# Multiplier.net
KiCad netlist of a schematic drawn in EAGLE
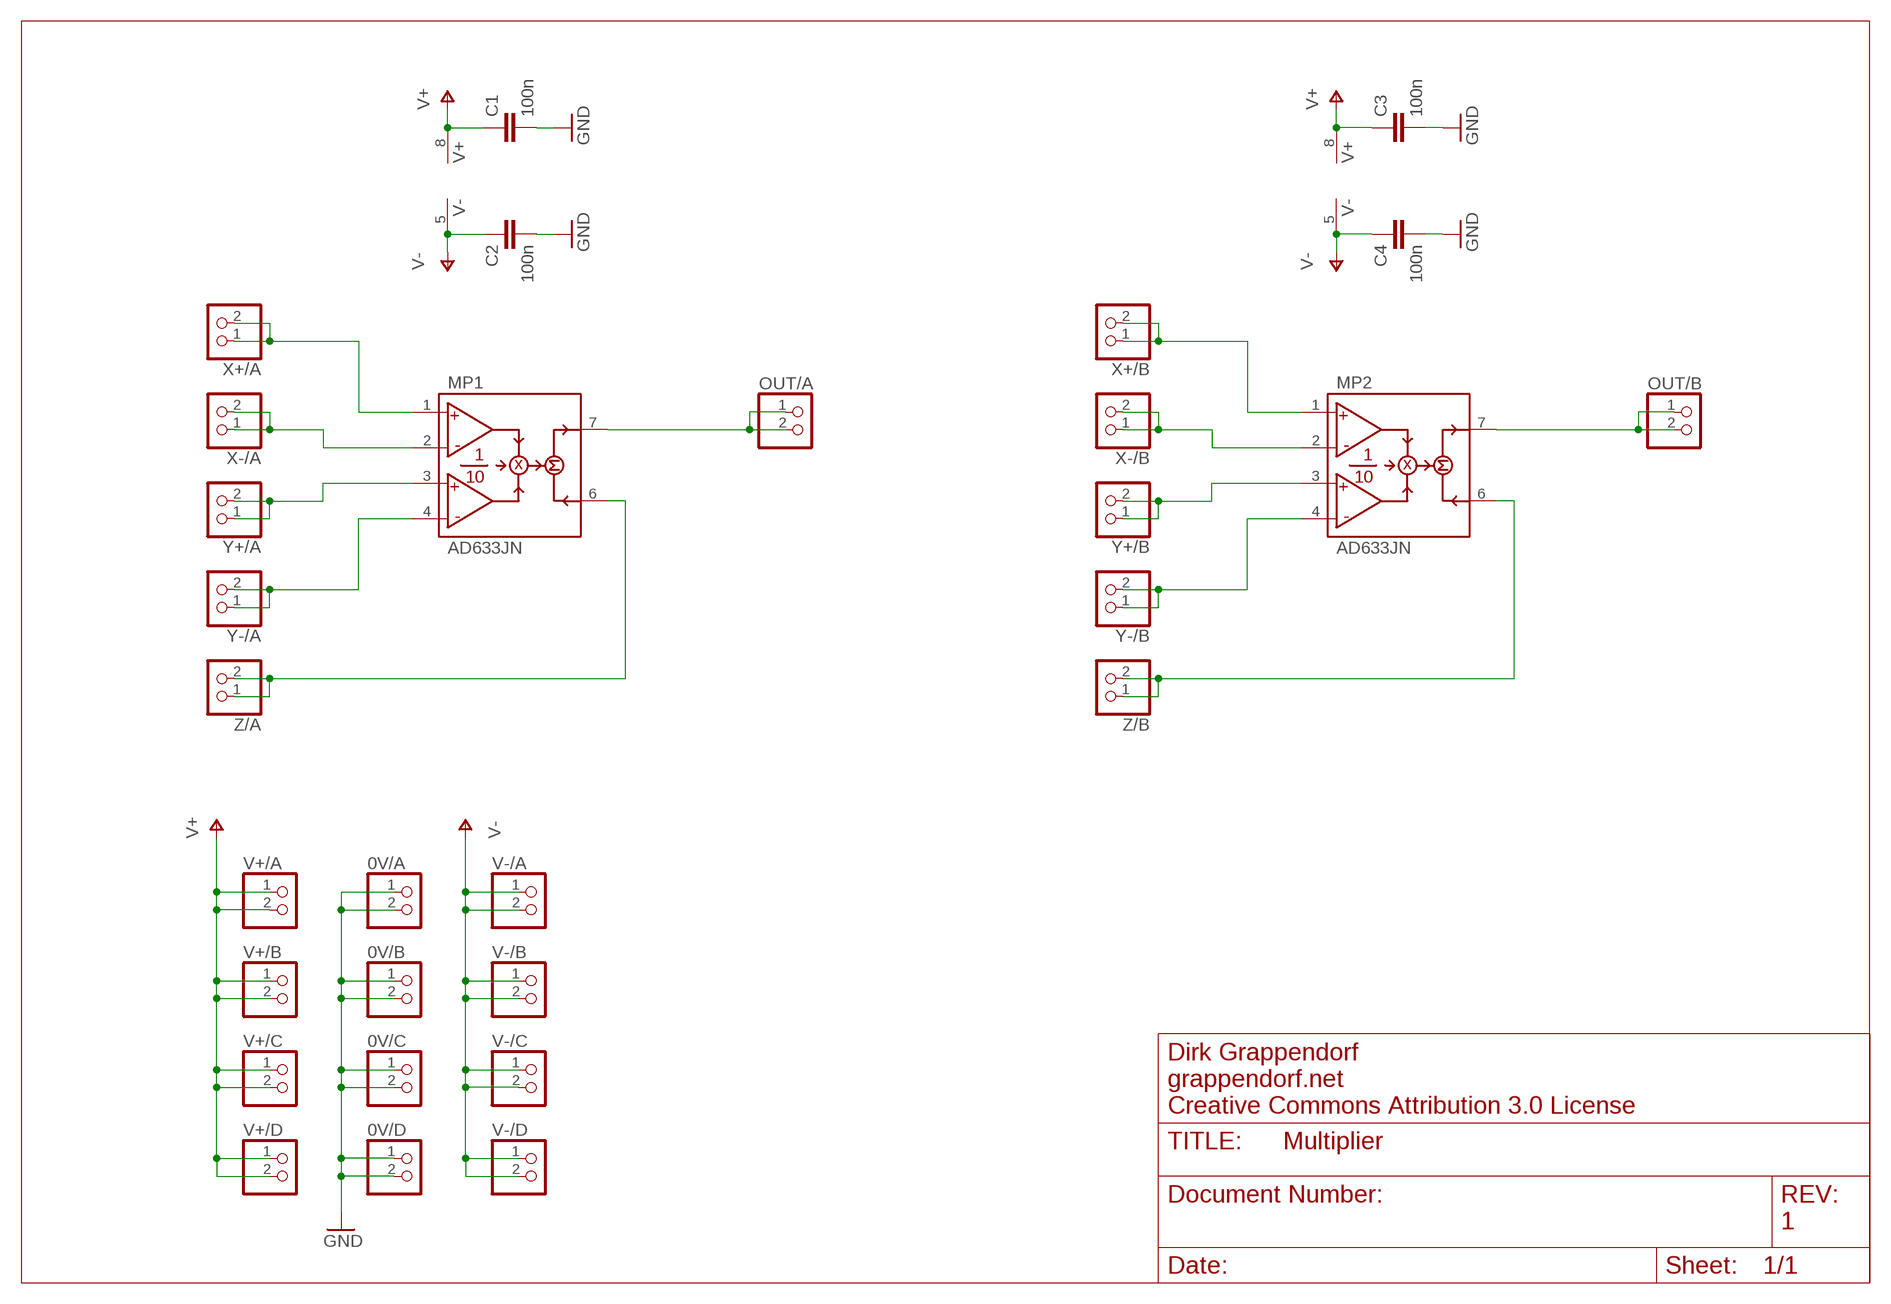
[diagram p0: schematic, sheet 1]

(export (version "E")
  (design (tool "Eeschema 10.0.6"))
  (components
    (comp (ref "0V/A")
      (value "PINHD-1X2")
      (footprint "eagle-import:1X02")
      (libsource (lib "eagle-import") (part "PINHD-1X2"))
    )
    (comp (ref "0V/B")
      (value "PINHD-1X2")
      (footprint "eagle-import:1X02")
      (libsource (lib "eagle-import") (part "PINHD-1X2"))
    )
    (comp (ref "0V/C")
      (value "PINHD-1X2")
      (footprint "eagle-import:1X02")
      (libsource (lib "eagle-import") (part "PINHD-1X2"))
    )
    (comp (ref "0V/D")
      (value "PINHD-1X2")
      (footprint "eagle-import:1X02")
      (libsource (lib "eagle-import") (part "PINHD-1X2"))
    )
    (comp (ref "C1")
      (value "100n")
      (footprint "eagle-import:C025-025X050")
      (libsource (lib "eagle-import") (part "C-EU025-025X050"))
    )
    (comp (ref "C2")
      (value "100n")
      (footprint "eagle-import:C025-025X050")
      (libsource (lib "eagle-import") (part "C-EU025-025X050"))
    )
    (comp (ref "C3")
      (value "100n")
      (footprint "eagle-import:C025-025X050")
      (libsource (lib "eagle-import") (part "C-EU025-025X050"))
    )
    (comp (ref "C4")
      (value "100n")
      (footprint "eagle-import:C025-025X050")
      (libsource (lib "eagle-import") (part "C-EU025-025X050"))
    )
    (comp (ref "MP1")
      (value "AD633JN")
      (footprint "eagle-import:DIL08")
      (libsource (lib "eagle-import") (part "AD633NJ"))
    )
    (comp (ref "MP2")
      (value "AD633JN")
      (footprint "eagle-import:DIL08")
      (libsource (lib "eagle-import") (part "AD633NJ"))
    )
    (comp (ref "OUT/A")
      (value "PINHD-1X2")
      (footprint "eagle-import:1X02")
      (libsource (lib "eagle-import") (part "PINHD-1X2"))
    )
    (comp (ref "OUT/B")
      (value "PINHD-1X2")
      (footprint "eagle-import:1X02")
      (libsource (lib "eagle-import") (part "PINHD-1X2"))
    )
    (comp (ref "V+/A")
      (value "PINHD-1X2")
      (footprint "eagle-import:1X02")
      (libsource (lib "eagle-import") (part "PINHD-1X2"))
    )
    (comp (ref "V+/B")
      (value "PINHD-1X2")
      (footprint "eagle-import:1X02")
      (libsource (lib "eagle-import") (part "PINHD-1X2"))
    )
    (comp (ref "V+/C")
      (value "PINHD-1X2")
      (footprint "eagle-import:1X02")
      (libsource (lib "eagle-import") (part "PINHD-1X2"))
    )
    (comp (ref "V+/D")
      (value "PINHD-1X2")
      (footprint "eagle-import:1X02")
      (libsource (lib "eagle-import") (part "PINHD-1X2"))
    )
    (comp (ref "V-/A")
      (value "PINHD-1X2")
      (footprint "eagle-import:1X02")
      (libsource (lib "eagle-import") (part "PINHD-1X2"))
    )
    (comp (ref "V-/B")
      (value "PINHD-1X2")
      (footprint "eagle-import:1X02")
      (libsource (lib "eagle-import") (part "PINHD-1X2"))
    )
    (comp (ref "V-/C")
      (value "PINHD-1X2")
      (footprint "eagle-import:1X02")
      (libsource (lib "eagle-import") (part "PINHD-1X2"))
    )
    (comp (ref "V-/D")
      (value "PINHD-1X2")
      (footprint "eagle-import:1X02")
      (libsource (lib "eagle-import") (part "PINHD-1X2"))
    )
    (comp (ref "X+/A")
      (value "PINHD-1X2")
      (footprint "eagle-import:1X02")
      (libsource (lib "eagle-import") (part "PINHD-1X2"))
    )
    (comp (ref "X+/B")
      (value "PINHD-1X2")
      (footprint "eagle-import:1X02")
      (libsource (lib "eagle-import") (part "PINHD-1X2"))
    )
    (comp (ref "X-/A")
      (value "PINHD-1X2")
      (footprint "eagle-import:1X02")
      (libsource (lib "eagle-import") (part "PINHD-1X2"))
    )
    (comp (ref "X-/B")
      (value "PINHD-1X2")
      (footprint "eagle-import:1X02")
      (libsource (lib "eagle-import") (part "PINHD-1X2"))
    )
    (comp (ref "Y+/A")
      (value "PINHD-1X2")
      (footprint "eagle-import:1X02")
      (libsource (lib "eagle-import") (part "PINHD-1X2"))
    )
    (comp (ref "Y+/B")
      (value "PINHD-1X2")
      (footprint "eagle-import:1X02")
      (libsource (lib "eagle-import") (part "PINHD-1X2"))
    )
    (comp (ref "Y-/A")
      (value "PINHD-1X2")
      (footprint "eagle-import:1X02")
      (libsource (lib "eagle-import") (part "PINHD-1X2"))
    )
    (comp (ref "Y-/B")
      (value "PINHD-1X2")
      (footprint "eagle-import:1X02")
      (libsource (lib "eagle-import") (part "PINHD-1X2"))
    )
    (comp (ref "Z/A")
      (value "PINHD-1X2")
      (footprint "eagle-import:1X02")
      (libsource (lib "eagle-import") (part "PINHD-1X2"))
    )
    (comp (ref "Z/B")
      (value "PINHD-1X2")
      (footprint "eagle-import:1X02")
      (libsource (lib "eagle-import") (part "PINHD-1X2"))
    )
  )
  (nets
    (net (code "1") (name "GND") (class "Default")
      (node (ref "0V/A") (pin "1") (pinfunction "1_1") (pintype "passive"))
      (node (ref "0V/A") (pin "2") (pinfunction "2_2") (pintype "passive"))
      (node (ref "0V/B") (pin "1") (pinfunction "1_1") (pintype "passive"))
      (node (ref "0V/B") (pin "2") (pinfunction "2_2") (pintype "passive"))
      (node (ref "0V/C") (pin "1") (pinfunction "1_1") (pintype "passive"))
      (node (ref "0V/C") (pin "2") (pinfunction "2_2") (pintype "passive"))
      (node (ref "0V/D") (pin "1") (pinfunction "1_1") (pintype "passive"))
      (node (ref "0V/D") (pin "2") (pinfunction "2_2") (pintype "passive"))
      (node (ref "C1") (pin "2") (pinfunction "2_2") (pintype "passive"))
      (node (ref "C2") (pin "2") (pinfunction "2_2") (pintype "passive"))
      (node (ref "C3") (pin "2") (pinfunction "2_2") (pintype "passive"))
      (node (ref "C4") (pin "2") (pinfunction "2_2") (pintype "passive"))
    )
    (net (code "2") (name "Net-(MP1A-W)") (class "Default")
      (node (ref "MP1") (pin "7") (pinfunction "W_7") (pintype "output"))
      (node (ref "OUT/A") (pin "1") (pinfunction "1_1") (pintype "passive"))
      (node (ref "OUT/A") (pin "2") (pinfunction "2_2") (pintype "passive"))
    )
    (net (code "3") (name "Net-(MP1A-X1)") (class "Default")
      (node (ref "MP1") (pin "1") (pinfunction "X1_1") (pintype "input"))
      (node (ref "X+/A") (pin "1") (pinfunction "1_1") (pintype "passive"))
      (node (ref "X+/A") (pin "2") (pinfunction "2_2") (pintype "passive"))
    )
    (net (code "4") (name "Net-(MP1A-X2)") (class "Default")
      (node (ref "MP1") (pin "2") (pinfunction "X2_2") (pintype "input"))
      (node (ref "X-/A") (pin "1") (pinfunction "1_1") (pintype "passive"))
      (node (ref "X-/A") (pin "2") (pinfunction "2_2") (pintype "passive"))
    )
    (net (code "5") (name "Net-(MP1A-Y1)") (class "Default")
      (node (ref "MP1") (pin "3") (pinfunction "Y1_3") (pintype "input"))
      (node (ref "Y+/A") (pin "1") (pinfunction "1_1") (pintype "passive"))
      (node (ref "Y+/A") (pin "2") (pinfunction "2_2") (pintype "passive"))
    )
    (net (code "6") (name "Net-(MP1A-Y2)") (class "Default")
      (node (ref "MP1") (pin "4") (pinfunction "Y2_4") (pintype "input"))
      (node (ref "Y-/A") (pin "1") (pinfunction "1_1") (pintype "passive"))
      (node (ref "Y-/A") (pin "2") (pinfunction "2_2") (pintype "passive"))
    )
    (net (code "7") (name "Net-(MP1A-Z)") (class "Default")
      (node (ref "MP1") (pin "6") (pinfunction "Z_6") (pintype "input"))
      (node (ref "Z/A") (pin "1") (pinfunction "1_1") (pintype "passive"))
      (node (ref "Z/A") (pin "2") (pinfunction "2_2") (pintype "passive"))
    )
    (net (code "8") (name "Net-(MP2A-W)") (class "Default")
      (node (ref "MP2") (pin "7") (pinfunction "W_7") (pintype "output"))
      (node (ref "OUT/B") (pin "1") (pinfunction "1_1") (pintype "passive"))
      (node (ref "OUT/B") (pin "2") (pinfunction "2_2") (pintype "passive"))
    )
    (net (code "9") (name "Net-(MP2A-X1)") (class "Default")
      (node (ref "MP2") (pin "1") (pinfunction "X1_1") (pintype "input"))
      (node (ref "X+/B") (pin "1") (pinfunction "1_1") (pintype "passive"))
      (node (ref "X+/B") (pin "2") (pinfunction "2_2") (pintype "passive"))
    )
    (net (code "10") (name "Net-(MP2A-X2)") (class "Default")
      (node (ref "MP2") (pin "2") (pinfunction "X2_2") (pintype "input"))
      (node (ref "X-/B") (pin "1") (pinfunction "1_1") (pintype "passive"))
      (node (ref "X-/B") (pin "2") (pinfunction "2_2") (pintype "passive"))
    )
    (net (code "11") (name "Net-(MP2A-Y1)") (class "Default")
      (node (ref "MP2") (pin "3") (pinfunction "Y1_3") (pintype "input"))
      (node (ref "Y+/B") (pin "1") (pinfunction "1_1") (pintype "passive"))
      (node (ref "Y+/B") (pin "2") (pinfunction "2_2") (pintype "passive"))
    )
    (net (code "12") (name "Net-(MP2A-Y2)") (class "Default")
      (node (ref "MP2") (pin "4") (pinfunction "Y2_4") (pintype "input"))
      (node (ref "Y-/B") (pin "1") (pinfunction "1_1") (pintype "passive"))
      (node (ref "Y-/B") (pin "2") (pinfunction "2_2") (pintype "passive"))
    )
    (net (code "13") (name "Net-(MP2A-Z)") (class "Default")
      (node (ref "MP2") (pin "6") (pinfunction "Z_6") (pintype "input"))
      (node (ref "Z/B") (pin "1") (pinfunction "1_1") (pintype "passive"))
      (node (ref "Z/B") (pin "2") (pinfunction "2_2") (pintype "passive"))
    )
    (net (code "14") (name "V+") (class "Default")
      (node (ref "C1") (pin "1") (pinfunction "1_1") (pintype "passive"))
      (node (ref "C3") (pin "1") (pinfunction "1_1") (pintype "passive"))
      (node (ref "MP1") (pin "8") (pinfunction "V+_8") (pintype "power_in"))
      (node (ref "MP2") (pin "8") (pinfunction "V+_8") (pintype "power_in"))
      (node (ref "V+/A") (pin "1") (pinfunction "1_1") (pintype "passive"))
      (node (ref "V+/A") (pin "2") (pinfunction "2_2") (pintype "passive"))
      (node (ref "V+/B") (pin "1") (pinfunction "1_1") (pintype "passive"))
      (node (ref "V+/B") (pin "2") (pinfunction "2_2") (pintype "passive"))
      (node (ref "V+/C") (pin "1") (pinfunction "1_1") (pintype "passive"))
      (node (ref "V+/C") (pin "2") (pinfunction "2_2") (pintype "passive"))
      (node (ref "V+/D") (pin "1") (pinfunction "1_1") (pintype "passive"))
      (node (ref "V+/D") (pin "2") (pinfunction "2_2") (pintype "passive"))
    )
    (net (code "15") (name "V-") (class "Default")
      (node (ref "C2") (pin "1") (pinfunction "1_1") (pintype "passive"))
      (node (ref "C4") (pin "1") (pinfunction "1_1") (pintype "passive"))
      (node (ref "MP1") (pin "5") (pinfunction "V-_5") (pintype "power_in"))
      (node (ref "MP2") (pin "5") (pinfunction "V-_5") (pintype "power_in"))
      (node (ref "V-/A") (pin "1") (pinfunction "1_1") (pintype "passive"))
      (node (ref "V-/A") (pin "2") (pinfunction "2_2") (pintype "passive"))
      (node (ref "V-/B") (pin "1") (pinfunction "1_1") (pintype "passive"))
      (node (ref "V-/B") (pin "2") (pinfunction "2_2") (pintype "passive"))
      (node (ref "V-/C") (pin "1") (pinfunction "1_1") (pintype "passive"))
      (node (ref "V-/C") (pin "2") (pinfunction "2_2") (pintype "passive"))
      (node (ref "V-/D") (pin "1") (pinfunction "1_1") (pintype "passive"))
      (node (ref "V-/D") (pin "2") (pinfunction "2_2") (pintype "passive"))
    )
  )
)
